# RS485_Channel_3.net
KiCad netlist of a schematic drawn in Altium Designer
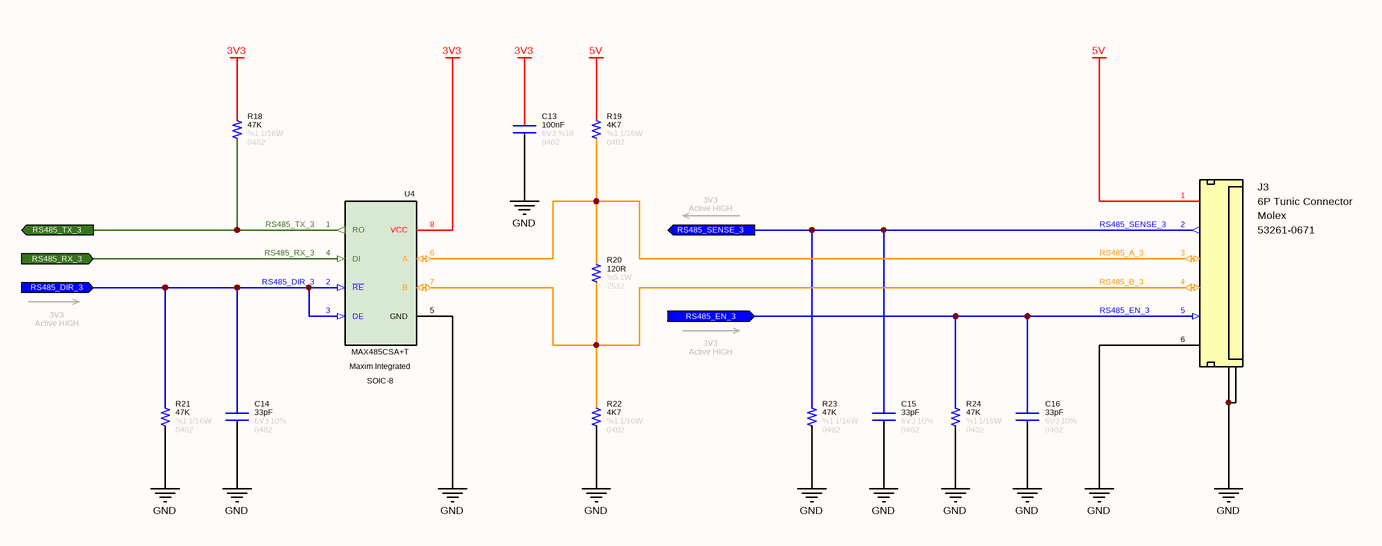
[diagram p0: RS485 Channel 3.SchDoc]

(export (version "E")
  (design (tool "Eeschema 10.0.6"))
  (components
    (comp (ref "C13")
      (value "100nF")
      (footprint "CAPACITOR_0402")
      (description "Capacitor - 100nF [0402-6V3] (Ceramic)")
      (fields
        (field (name "MANUFACTURER PART NUMBER") "04026D104KAT4A")
        (field (name "TOLERANCE") "%10")
        (field (name "VOLTAGE") "6V3")
        (field (name "CASE") "0402")
        (field (name "Comment") "Capacitor - 100nF [0402] (Ceramic)")
      )
      (libsource (lib "Akkoyun") (part "Capacitor - 100nF [0402-6V3]"))
    )
    (comp (ref "C14")
      (value "33pF")
      (footprint "CAPACITOR_0402")
      (description "Capacitor - 33pF [0402] (Ceramic)")
      (fields
        (field (name "MANUFACTURER PART NUMBER") "C0402C330J9RACAUTO")
        (field (name "TOLERANCE") "10%")
        (field (name "CASE") "0402")
        (field (name "VOLTAGE") "6V3")
      )
      (libsource (lib "Akkoyun") (part "Capacitor - 33pF [0402-6V3]"))
    )
    (comp (ref "C15")
      (value "33pF")
      (footprint "CAPACITOR_0402")
      (description "Capacitor - 33pF [0402] (Ceramic)")
      (fields
        (field (name "MANUFACTURER PART NUMBER") "C0402C330J9RACAUTO")
        (field (name "TOLERANCE") "10%")
        (field (name "CASE") "0402")
        (field (name "VOLTAGE") "6V3")
      )
      (libsource (lib "Akkoyun") (part "Capacitor - 33pF [0402-6V3]"))
    )
    (comp (ref "C16")
      (value "33pF")
      (footprint "CAPACITOR_0402")
      (description "Capacitor - 33pF [0402] (Ceramic)")
      (fields
        (field (name "MANUFACTURER PART NUMBER") "C0402C330J9RACAUTO")
        (field (name "TOLERANCE") "10%")
        (field (name "CASE") "0402")
        (field (name "VOLTAGE") "6V3")
      )
      (libsource (lib "Akkoyun") (part "Capacitor - 33pF [0402-6V3]"))
    )
    (comp (ref "J3")
      (value "6P Tunic Connector")
      (footprint "Connector_Tunic 6P")
      (description "Mini Tunic Connector with 6P")
      (fields
        (field (name "MANUFACTURER PART NUMBER") "53261-0671")
        (field (name "MANUFACTURER NAME") "Molex")
      )
      (libsource (lib "Akkoyun") (part "Connector - Mini Tunic 6P (1.25)"))
    )
    (comp (ref "R18")
      (value "47K")
      (footprint "RESISTOR_0402")
      (description "Thick Film Resistors - SMD 1/16 W 47 KOhm 1%")
      (fields
        (field (name "MANUFACTURER PART NUMBER") "CRCW040247K0FKED")
        (field (name "TOLERANCE") "%1")
        (field (name "CASE") "0402")
        (field (name "POWER") "1/16W")
        (field (name "Comment") "47K - 0402 - %1 - 1/16W")
      )
      (libsource (lib "Akkoyun") (part "Resistor - 47K [0402]"))
    )
    (comp (ref "R19")
      (value "4K7")
      (footprint "RESISTOR_0402")
      (description "Thick Film Resistors - SMD 1/16 W 4.7 KOhm 1%")
      (fields
        (field (name "MANUFACTURER PART NUMBER") "CRCW04024K70FKED")
        (field (name "TOLERANCE") "%1")
        (field (name "CASE") "0402")
        (field (name "POWER") "1/16W")
        (field (name "Comment") "4K7 - 0402 - %1 - 1/16W")
      )
      (libsource (lib "Akkoyun") (part "Resistor - 4K7 [0402]"))
    )
    (comp (ref "R20")
      (value "120R")
      (footprint "RESISTOR_2512")
      (description "Thick Film Resistors - SMD 1 W 120 Ohm 5%")
      (fields
        (field (name "MANUFACTURER PART NUMBER") "RC2512JK-07120RL")
        (field (name "TOLERANCE") "%5")
        (field (name "CASE") "2512")
        (field (name "POWER") "1W")
        (field (name "Comment") "120R - 2512 - %5 - 1W")
      )
      (libsource (lib "Akkoyun") (part "Resistor - 120R [2512]"))
    )
    (comp (ref "R21")
      (value "47K")
      (footprint "RESISTOR_0402")
      (description "Thick Film Resistors - SMD 1/16 W 47 KOhm 1%")
      (fields
        (field (name "MANUFACTURER PART NUMBER") "CRCW040247K0FKED")
        (field (name "TOLERANCE") "%1")
        (field (name "CASE") "0402")
        (field (name "POWER") "1/16W")
        (field (name "Comment") "47K - 0402 - %1 - 1/16W")
      )
      (libsource (lib "Akkoyun") (part "Resistor - 47K [0402]"))
    )
    (comp (ref "R22")
      (value "4K7")
      (footprint "RESISTOR_0402")
      (description "Thick Film Resistors - SMD 1/16 W 4.7 KOhm 1%")
      (fields
        (field (name "MANUFACTURER PART NUMBER") "CRCW04024K70FKED")
        (field (name "TOLERANCE") "%1")
        (field (name "CASE") "0402")
        (field (name "POWER") "1/16W")
        (field (name "Comment") "4K7 - 0402 - %1 - 1/16W")
      )
      (libsource (lib "Akkoyun") (part "Resistor - 4K7 [0402]"))
    )
    (comp (ref "R23")
      (value "47K")
      (footprint "RESISTOR_0402")
      (description "Thick Film Resistors - SMD 1/16 W 47 KOhm 1%")
      (fields
        (field (name "MANUFACTURER PART NUMBER") "CRCW040247K0FKED")
        (field (name "TOLERANCE") "%1")
        (field (name "CASE") "0402")
        (field (name "POWER") "1/16W")
        (field (name "Comment") "47K - 0402 - %1 - 1/16W")
      )
      (libsource (lib "Akkoyun") (part "Resistor - 47K [0402]"))
    )
    (comp (ref "R24")
      (value "47K")
      (footprint "RESISTOR_0402")
      (description "Thick Film Resistors - SMD 1/16 W 47 KOhm 1%")
      (fields
        (field (name "MANUFACTURER PART NUMBER") "CRCW040247K0FKED")
        (field (name "TOLERANCE") "%1")
        (field (name "CASE") "0402")
        (field (name "POWER") "1/16W")
        (field (name "Comment") "47K - 0402 - %1 - 1/16W")
      )
      (libsource (lib "Akkoyun") (part "Resistor - 47K [0402]"))
    )
    (comp (ref "U4")
      (value "RS485 Modulator")
      (footprint "SOP-8L (AZRS3080E)")
      (description "RS-422/RS-485 Interface IC Low-Power, Slew-Rate-Limited RS-485/RS-422 Transceivers")
      (fields
        (field (name "CASE") "SOIC-8")
        (field (name "MANUFACTURER PART NUMBER") "MAX485CSA+T")
        (field (name "MANUFACTURER NAME") "Maxim Integrated")
      )
      (libsource (lib "Akkoyun") (part "IC - MAX485CSA+T"))
    )
  )
  (nets
    (net (code "1") (name "/RS485_A_3") (class "Default")
      (node (ref "J3") (pin "3") (pinfunction "RS485-A_3") (pintype "bidirectional"))
      (node (ref "R19") (pin "1") (pinfunction "1_1") (pintype "passive"))
      (node (ref "R20") (pin "2") (pinfunction "2_2") (pintype "passive"))
      (node (ref "U4") (pin "6") (pinfunction "A_6") (pintype "bidirectional"))
    )
    (net (code "2") (name "/RS485_B_3") (class "Default")
      (node (ref "J3") (pin "4") (pinfunction "RS485-B_4") (pintype "bidirectional"))
      (node (ref "R20") (pin "1") (pinfunction "1_1") (pintype "passive"))
      (node (ref "R22") (pin "2") (pinfunction "2_2") (pintype "passive"))
      (node (ref "U4") (pin "7") (pinfunction "B_7") (pintype "bidirectional"))
    )
    (net (code "3") (name "/RS485_DIR_3") (class "Default")
      (node (ref "C14") (pin "2") (pinfunction "2_2") (pintype "passive"))
      (node (ref "R21") (pin "2") (pinfunction "2_2") (pintype "passive"))
      (node (ref "U4") (pin "2") (pinfunction "~{RE}_2") (pintype "input"))
      (node (ref "U4") (pin "3") (pinfunction "DE_3") (pintype "input"))
    )
    (net (code "4") (name "/RS485_EN_3") (class "Default")
      (node (ref "C16") (pin "2") (pinfunction "2_2") (pintype "passive"))
      (node (ref "J3") (pin "5") (pinfunction "INT_5") (pintype "input"))
      (node (ref "R24") (pin "2") (pinfunction "2_2") (pintype "passive"))
    )
    (net (code "5") (name "/RS485_RX_3") (class "Default")
      (node (ref "U4") (pin "4") (pinfunction "DI_4") (pintype "input"))
    )
    (net (code "6") (name "/RS485_SENSE_3") (class "Default")
      (node (ref "C15") (pin "2") (pinfunction "2_2") (pintype "passive"))
      (node (ref "J3") (pin "2") (pinfunction "Sense_2") (pintype "output"))
      (node (ref "R23") (pin "2") (pinfunction "2_2") (pintype "passive"))
    )
    (net (code "7") (name "/RS485_TX_3") (class "Default")
      (node (ref "R18") (pin "1") (pinfunction "1_1") (pintype "passive"))
      (node (ref "U4") (pin "1") (pinfunction "RO_1") (pintype "output"))
    )
    (net (code "8") (name "3V3") (class "Default")
      (node (ref "C13") (pin "2") (pinfunction "2_2") (pintype "passive"))
      (node (ref "R18") (pin "2") (pinfunction "2_2") (pintype "passive"))
      (node (ref "U4") (pin "8") (pinfunction "VCC_8") (pintype "power_in"))
    )
    (net (code "9") (name "5V") (class "Default")
      (node (ref "J3") (pin "1") (pinfunction "5V_1") (pintype "power_in"))
      (node (ref "R19") (pin "2") (pinfunction "2_2") (pintype "passive"))
    )
    (net (code "10") (name "GND") (class "Default")
      (node (ref "C13") (pin "1") (pinfunction "1_1") (pintype "passive"))
      (node (ref "C14") (pin "1") (pinfunction "1_1") (pintype "passive"))
      (node (ref "C15") (pin "1") (pinfunction "1_1") (pintype "passive"))
      (node (ref "C16") (pin "1") (pinfunction "1_1") (pintype "passive"))
      (node (ref "J3") (pin "6") (pinfunction "GND_6") (pintype "power_in"))
      (node (ref "J3") (pin "7") (pinfunction "GND_7") (pintype "passive"))
      (node (ref "J3") (pin "8") (pinfunction "GND_8") (pintype "passive"))
      (node (ref "R21") (pin "1") (pinfunction "1_1") (pintype "passive"))
      (node (ref "R22") (pin "1") (pinfunction "1_1") (pintype "passive"))
      (node (ref "R23") (pin "1") (pinfunction "1_1") (pintype "passive"))
      (node (ref "R24") (pin "1") (pinfunction "1_1") (pintype "passive"))
      (node (ref "U4") (pin "5") (pinfunction "GND_5") (pintype "passive"))
    )
  )
)
